# pqm_v2_page5.net
KiCad netlist of a schematic drawn in Altium Designer
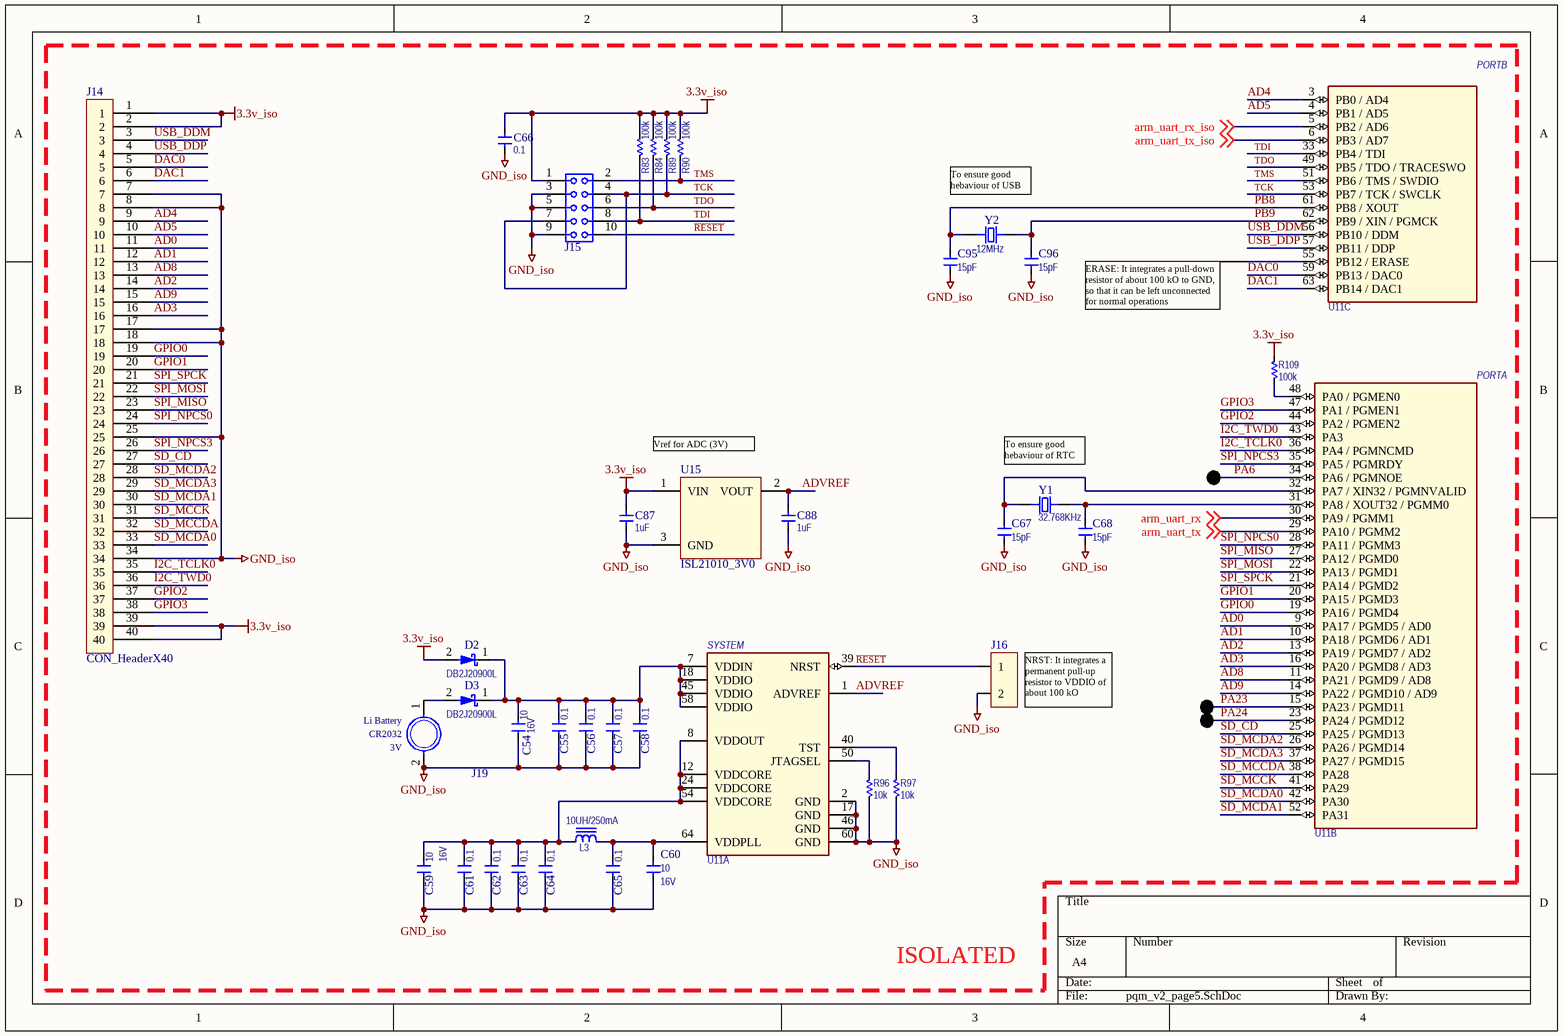
[diagram p0: pqm_v2_page5.SchDoc]

(export (version "E")
  (design (tool "Eeschema 10.0.6"))
  (components
    (comp (ref "C54")
      (value "10")
      (footprint "CAPC2013X110N")
      (description "CAP CER 10UF 16V 10% X6S 0805")
      (fields
        (field (name "MANUFACTURER") "TDK Corporation")
        (field (name "TOLERANCE") "10%")
        (field (name "VOLTAGE RATING") "16V")
      )
      (libsource (lib "pqm_v2_lib_cap") (part "CAP_C2012X6S1C106K085AC_TDK"))
    )
    (comp (ref "C55")
      (value "0.1")
      (footprint "CAPC2013X110N")
      (description "CAP CER 0.1UF 25V 10% X7R 0805")
      (fields (field (name "MANUFACTURER") "Yageo") (field (name "TOLERANCE") "10%"))
      (libsource (lib "pqm_v2_lib_cap") (part "CAP_CC0805KRX7R8BB104_YAGEO"))
    )
    (comp (ref "C56")
      (value "0.1")
      (footprint "CAPC2013X110N")
      (description "CAP CER 0.1UF 25V 10% X7R 0805")
      (fields (field (name "MANUFACTURER") "Yageo") (field (name "TOLERANCE") "10%"))
      (libsource (lib "pqm_v2_lib_cap") (part "CAP_CC0805KRX7R8BB104_YAGEO"))
    )
    (comp (ref "C57")
      (value "0.1")
      (footprint "CAPC2013X110N")
      (description "CAP CER 0.1UF 25V 10% X7R 0805")
      (fields (field (name "MANUFACTURER") "Yageo") (field (name "TOLERANCE") "10%"))
      (libsource (lib "pqm_v2_lib_cap") (part "CAP_CC0805KRX7R8BB104_YAGEO"))
    )
    (comp (ref "C58")
      (value "0.1")
      (footprint "CAPC2013X110N")
      (description "CAP CER 0.1UF 25V 10% X7R 0805")
      (fields (field (name "MANUFACTURER") "Yageo") (field (name "TOLERANCE") "10%"))
      (libsource (lib "pqm_v2_lib_cap") (part "CAP_CC0805KRX7R8BB104_YAGEO"))
    )
    (comp (ref "C59")
      (value "10")
      (footprint "CAPC2013X110N")
      (description "CAP CER 10UF 16V 10% X6S 0805")
      (fields
        (field (name "MANUFACTURER") "TDK Corporation")
        (field (name "TOLERANCE") "10%")
        (field (name "VOLTAGE RATING") "16V")
      )
      (libsource (lib "pqm_v2_lib_cap") (part "CAP_C2012X6S1C106K085AC_TDK"))
    )
    (comp (ref "C60")
      (value "10")
      (footprint "CAPC2013X110N")
      (description "CAP CER 10UF 16V 10% X6S 0805")
      (fields
        (field (name "MANUFACTURER") "TDK Corporation")
        (field (name "TOLERANCE") "10%")
        (field (name "VOLTAGE RATING") "16V")
      )
      (libsource (lib "pqm_v2_lib_cap") (part "CAP_C2012X6S1C106K085AC_TDK"))
    )
    (comp (ref "C61")
      (value "0.1")
      (footprint "CAPC2013X110N")
      (description "CAP CER 0.1UF 25V 10% X7R 0805")
      (fields (field (name "MANUFACTURER") "Yageo") (field (name "TOLERANCE") "10%"))
      (libsource (lib "pqm_v2_lib_cap") (part "CAP_CC0805KRX7R8BB104_YAGEO"))
    )
    (comp (ref "C62")
      (value "0.1")
      (footprint "CAPC2013X110N")
      (description "CAP CER 0.1UF 25V 10% X7R 0805")
      (fields (field (name "MANUFACTURER") "Yageo") (field (name "TOLERANCE") "10%"))
      (libsource (lib "pqm_v2_lib_cap") (part "CAP_CC0805KRX7R8BB104_YAGEO"))
    )
    (comp (ref "C63")
      (value "0.1")
      (footprint "CAPC2013X110N")
      (description "CAP CER 0.1UF 25V 10% X7R 0805")
      (fields (field (name "MANUFACTURER") "Yageo") (field (name "TOLERANCE") "10%"))
      (libsource (lib "pqm_v2_lib_cap") (part "CAP_CC0805KRX7R8BB104_YAGEO"))
    )
    (comp (ref "C64")
      (value "0.1")
      (footprint "CAPC2013X110N")
      (description "CAP CER 0.1UF 25V 10% X7R 0805")
      (fields (field (name "MANUFACTURER") "Yageo") (field (name "TOLERANCE") "10%"))
      (libsource (lib "pqm_v2_lib_cap") (part "CAP_CC0805KRX7R8BB104_YAGEO"))
    )
    (comp (ref "C65")
      (value "0.1")
      (footprint "CAPC2013X110N")
      (description "CAP CER 0.1UF 25V 10% X7R 0805")
      (fields (field (name "MANUFACTURER") "Yageo") (field (name "TOLERANCE") "10%"))
      (libsource (lib "pqm_v2_lib_cap") (part "CAP_CC0805KRX7R8BB104_YAGEO"))
    )
    (comp (ref "C66")
      (value "0.1")
      (footprint "CAPC2013X110N")
      (description "CAP CER 0.1UF 25V 10% X7R 0805")
      (fields (field (name "MANUFACTURER") "Yageo") (field (name "TOLERANCE") "10%"))
      (libsource (lib "pqm_v2_lib_cap") (part "CAP_CC0805KRX7R8BB104_YAGEO"))
    )
    (comp (ref "C67")
      (value "15pF")
      (footprint "CAPC2013X110N")
      (description "CAP CER 15PF 50V NP0 0805")
      (fields (field (name "MANUFACTURER") "Kemet") (field (name "DIGIKEY PART NUMBER") "399-7428-1-ND"))
      (libsource (lib "pqm_v2_lib_cap") (part "CAP_C0805X150J5GACTU_KEMET"))
    )
    (comp (ref "C68")
      (value "15pF")
      (footprint "CAPC2013X110N")
      (description "CAP CER 15PF 50V NP0 0805")
      (fields (field (name "MANUFACTURER") "Kemet") (field (name "DIGIKEY PART NUMBER") "399-7428-1-ND"))
      (libsource (lib "pqm_v2_lib_cap") (part "CAP_C0805X150J5GACTU_KEMET"))
    )
    (comp (ref "C87")
      (value "1uF")
      (footprint "CAPC2013X110N")
      (description "CAP CER 1UF 16V X7R 0805")
      (fields (field (name "MANUFACTURER") "YAGEO") (field (name "TOLERANCE") "10%"))
      (libsource (lib "pqm_v2_lib_cap") (part "CAP_CC0805KKX7R7BB105_YAGEO"))
    )
    (comp (ref "C88")
      (value "1uF")
      (footprint "CAPC2013X110N")
      (description "CAP CER 1UF 16V X7R 0805")
      (fields (field (name "MANUFACTURER") "YAGEO") (field (name "TOLERANCE") "10%"))
      (libsource (lib "pqm_v2_lib_cap") (part "CAP_CC0805KKX7R7BB105_YAGEO"))
    )
    (comp (ref "C95")
      (value "15pF")
      (footprint "CAPC2013X110N")
      (description "CAP CER 15PF 50V NP0 0805")
      (fields (field (name "MANUFACTURER") "Kemet") (field (name "DIGIKEY PART NUMBER") "399-7428-1-ND"))
      (libsource (lib "pqm_v2_lib_cap") (part "CAP_C0805X150J5GACTU_KEMET"))
    )
    (comp (ref "C96")
      (value "15pF")
      (footprint "CAPC2013X110N")
      (description "CAP CER 15PF 50V NP0 0805")
      (fields (field (name "MANUFACTURER") "Kemet") (field (name "DIGIKEY PART NUMBER") "399-7428-1-ND"))
      (libsource (lib "pqm_v2_lib_cap") (part "CAP_C0805X150J5GACTU_KEMET"))
    )
    (comp (ref "D2")
      (value "DB2J20900L")
      (footprint "SOD2512X097N")
      (description "DIODE SCHOTTKY 20V 500MA SMINI2")
      (fields
        (field (name "MANUFACTURER") "Panasonic")
        (field (name "DIGIKEY PART NUMBER") "DB2J20900LCT-ND")
      )
      (libsource (lib "pqm_v2_lib_diodos") (part "DIO_DB2J20900L_PANASONIC"))
    )
    (comp (ref "D3")
      (value "DB2J20900L")
      (footprint "SOD2512X097N")
      (description "DIODE SCHOTTKY 20V 500MA SMINI2")
      (fields
        (field (name "MANUFACTURER") "Panasonic")
        (field (name "DIGIKEY PART NUMBER") "DB2J20900LCT-ND")
      )
      (libsource (lib "pqm_v2_lib_diodos") (part "DIO_DB2J20900L_PANASONIC"))
    )
    (comp (ref "J14")
      (value "CON_HeaderX40")
      (footprint "HeaderX70")
      (libsource (lib "pqm_v2_lib_connectors") (part "CON_HeaderX40"))
    )
    (comp (ref "J15")
      (value "CON_20021121-00010C4LF_FCI")
      (footprint "FCI_20021121-00010C4LF")
      (description "CONN HEADER 10POS DL UNSHRD SMD")
      (fields (field (name "MANUFACTURER") "FCI") (field (name "DIGIKEY PART NUMBER") "609-3695-1-ND"))
      (libsource (lib "pqm_v2_lib_connectors") (part "CON_20021121-00010C4LF_FCI"))
    )
    (comp (ref "J16")
      (value "CON_RADX2")
      (footprint "RAD2")
      (libsource (lib "pqm_v2_lib_connectors") (part "CON_RADX2"))
    )
    (comp (ref "J19")
      (value "CON_BAT")
      (footprint "CON_BAT_2032")
      (description "HOLDER COINCELL 2032 RETAINRCLIP")
      (fields
        (field (name "DIGIKEY PART NUMBER") "BS-7-ND")
        (field (name "MOUSER PART NUMBER") "122-2420-GR")
      )
      (libsource (lib "pqm_v2_lib_connectors") (part "CON_BAT"))
    )
    (comp (ref "L3")
      (value "10UH/250mA")
      (footprint "INDC4532X170N")
      (description "FIXED IND 10UH 2A 65 MOHM SMD")
      (fields
        (field (name "MANUFACTURER") "Bourns Inc")
        (field (name "DIGIKEY PART NUMBER") "CM453232-100KLCT-ND")
      )
      (libsource (lib "pqm_v2_lib_mag") (part "MAG_CM453232-100KLCT_BOURNS"))
    )
    (comp (ref "R83")
      (value "100k")
      (footprint "RESC2013X065BN")
      (description "RES SMD 100K OHM 5% 1/8W 0805")
      (fields (field (name "TOLERANCE") "5%") (field (name "MANUFACTURER") "Yageo"))
      (libsource (lib "pqm_v2_lib_res") (part "RES_AC0805JR-07100KL_YAGEO"))
    )
    (comp (ref "R84")
      (value "100k")
      (footprint "RESC2013X065BN")
      (description "RES SMD 100K OHM 5% 1/8W 0805")
      (fields (field (name "TOLERANCE") "5%") (field (name "MANUFACTURER") "Yageo"))
      (libsource (lib "pqm_v2_lib_res") (part "RES_AC0805JR-07100KL_YAGEO"))
    )
    (comp (ref "R89")
      (value "100k")
      (footprint "RESC2013X065BN")
      (description "RES SMD 100K OHM 5% 1/8W 0805")
      (fields (field (name "TOLERANCE") "5%") (field (name "MANUFACTURER") "Yageo"))
      (libsource (lib "pqm_v2_lib_res") (part "RES_AC0805JR-07100KL_YAGEO"))
    )
    (comp (ref "R90")
      (value "100k")
      (footprint "RESC2013X065BN")
      (description "RES SMD 100K OHM 5% 1/8W 0805")
      (fields (field (name "TOLERANCE") "5%") (field (name "MANUFACTURER") "Yageo"))
      (libsource (lib "pqm_v2_lib_res") (part "RES_AC0805JR-07100KL_YAGEO"))
    )
    (comp (ref "R96")
      (value "10k")
      (footprint "RESC2013X065BN")
      (description "RES SMD 10K OHM 5% 1/8W 0805")
      (fields (field (name "TOLERANCE") "5%") (field (name "MANUFACTURER") "Yageo"))
      (libsource (lib "pqm_v2_lib_res") (part "RES_RC0805JR-0710KL_YAGEO"))
    )
    (comp (ref "R97")
      (value "10k")
      (footprint "RESC2013X065BN")
      (description "RES SMD 10K OHM 5% 1/8W 0805")
      (fields (field (name "TOLERANCE") "5%") (field (name "MANUFACTURER") "Yageo"))
      (libsource (lib "pqm_v2_lib_res") (part "RES_RC0805JR-0710KL_YAGEO"))
    )
    (comp (ref "R109")
      (value "100k")
      (footprint "RESC2013X065BN")
      (description "RES SMD 100K OHM 5% 1/8W 0805")
      (fields (field (name "TOLERANCE") "5%") (field (name "MANUFACTURER") "Yageo"))
      (libsource (lib "pqm_v2_lib_res") (part "RES_AC0805JR-07100KL_YAGEO"))
    )
    (comp (ref "U11")
      (value "IC_ATSAM4S8BA-AU_ATMEL")
      (footprint "TQFP50P1000X1000X160-64N")
      (description "IC MCU 32BIT 512KB FLASH 64LQFP")
      (fields (field (name "MANUFACTURER") "Atmel") (field (name "DIGIKEY PART NUMBER") "ATSAM4S8BA-AU-ND"))
      (libsource (lib "") (part "IC_ATSAM4S8BA-AU_ATMEL_1"))
    )
    (comp (ref "U15")
      (value "ISL21010_3V0")
      (footprint "SOT23-3M")
      (description "IC VREF SERIES 3V SOT23-3")
      (fields
        (field (name "DIGIKEY PART NUMBER") "ISL21010CFH330Z-TKCT-ND")
        (field (name "MANUFACTURER PART NUMBER") "ISL21010CFH330Z-TK")
      )
      (libsource (lib "pqm_v2_lib_ic") (part "IC_ISL21010_3V0_INTERSIL"))
    )
    (comp (ref "Y1")
      (value "32.768KHz")
      (footprint "XTAL3215X090N")
      (description "CRYSTAL 32.7680KHZ 12.5PF SMD")
      (fields (field (name "MANUFACTURER") "ECS") (field (name "DIGIKEY PART NUMBER") "XC1967CT-ND"))
      (libsource (lib "pqm_v2_lib_connectors") (part "MSC_ECS-.327-12.5-34S-TR_ECS"))
    )
    (comp (ref "Y2")
      (value "12MHz")
      (footprint "CSM-3X")
      (description "12 MHz ±30 ppm Cristales 20 pF 60 Ohm -10°C ~ 70°C Montaje en superficie HC49/US")
      (fields (field (name "MANUFACTURER") "ECS Inc.") (field (name "DIGIKEY PART NUMBER") "XC1770DKR-ND"))
      (libsource (lib "pqm_v2_lib_connectors") (part "MSC_ECS-120-20-3X-TR_ECS"))
    )
  )
  (nets
    (net (code "1") (name "/AD0") (class "Default")
      (node (ref "J14") (pin "11") (pinfunction "11_11") (pintype "passive"))
      (node (ref "U11") (pin "9") (pinfunction "PA17_/_PGMD5_/_AD0_9") (pintype "bidirectional"))
    )
    (net (code "2") (name "/AD1") (class "Default")
      (node (ref "J14") (pin "12") (pinfunction "12_12") (pintype "passive"))
      (node (ref "U11") (pin "10") (pinfunction "PA18_/_PGMD6_/_AD1_10") (pintype "bidirectional"))
    )
    (net (code "3") (name "/AD2") (class "Default")
      (node (ref "J14") (pin "14") (pinfunction "14_14") (pintype "passive"))
      (node (ref "U11") (pin "13") (pinfunction "PA19_/_PGMD7_/_AD2_13") (pintype "bidirectional"))
    )
    (net (code "4") (name "/AD3") (class "Default")
      (node (ref "J14") (pin "16") (pinfunction "16_16") (pintype "passive"))
      (node (ref "U11") (pin "16") (pinfunction "PA20_/_PGMD8_/_AD3_16") (pintype "bidirectional"))
    )
    (net (code "5") (name "/AD4") (class "Default")
      (node (ref "J14") (pin "9") (pinfunction "9_9") (pintype "passive"))
      (node (ref "U11") (pin "3") (pinfunction "PB0_/_AD4_3") (pintype "bidirectional"))
    )
    (net (code "6") (name "/AD5") (class "Default")
      (node (ref "J14") (pin "10") (pinfunction "10_10") (pintype "passive"))
      (node (ref "U11") (pin "4") (pinfunction "PB1_/_AD5_4") (pintype "bidirectional"))
    )
    (net (code "7") (name "/AD8") (class "Default")
      (node (ref "J14") (pin "13") (pinfunction "13_13") (pintype "passive"))
      (node (ref "U11") (pin "11") (pinfunction "PA21_/_PGMD9_/_AD8_11") (pintype "bidirectional"))
    )
    (net (code "8") (name "/AD9") (class "Default")
      (node (ref "J14") (pin "15") (pinfunction "15_15") (pintype "passive"))
      (node (ref "U11") (pin "14") (pinfunction "PA22_/_PGMD10_/_AD9_14") (pintype "bidirectional"))
    )
    (net (code "9") (name "/ADVREF") (class "Default")
      (node (ref "C88") (pin "1") (pinfunction "T1_1") (pintype "passive"))
      (node (ref "U11") (pin "1") (pinfunction "ADVREF_1") (pintype "power_in"))
      (node (ref "U15") (pin "2") (pinfunction "VOUT_2") (pintype "passive"))
    )
    (net (code "10") (name "/DAC0") (class "Default")
      (node (ref "J14") (pin "5") (pinfunction "5_5") (pintype "passive"))
      (node (ref "U11") (pin "59") (pinfunction "PB13_/_DAC0_59") (pintype "bidirectional"))
    )
    (net (code "11") (name "/DAC1") (class "Default")
      (node (ref "J14") (pin "6") (pinfunction "6_6") (pintype "passive"))
      (node (ref "U11") (pin "63") (pinfunction "PB14_/_DAC1_63") (pintype "bidirectional"))
    )
    (net (code "12") (name "/GPIO0") (class "Default")
      (node (ref "J14") (pin "19") (pinfunction "19_19") (pintype "passive"))
      (node (ref "U11") (pin "19") (pinfunction "PA16_/_PGMD4_19") (pintype "bidirectional"))
    )
    (net (code "13") (name "/GPIO1") (class "Default")
      (node (ref "J14") (pin "20") (pinfunction "20_20") (pintype "passive"))
      (node (ref "U11") (pin "20") (pinfunction "PA15_/_PGMD3_20") (pintype "bidirectional"))
    )
    (net (code "14") (name "/GPIO2") (class "Default")
      (node (ref "J14") (pin "37") (pinfunction "37_37") (pintype "passive"))
      (node (ref "U11") (pin "44") (pinfunction "PA2_/_PGMEN2_44") (pintype "bidirectional"))
    )
    (net (code "15") (name "/GPIO3") (class "Default")
      (node (ref "J14") (pin "38") (pinfunction "38_38") (pintype "passive"))
      (node (ref "U11") (pin "47") (pinfunction "PA1_/_PGMEN1_47") (pintype "bidirectional"))
    )
    (net (code "16") (name "/I2C_TCLK0") (class "Default")
      (node (ref "J14") (pin "35") (pinfunction "35_35") (pintype "passive"))
      (node (ref "U11") (pin "36") (pinfunction "PA4_/_PGMNCMD_36") (pintype "bidirectional"))
    )
    (net (code "17") (name "/I2C_TWD0") (class "Default")
      (node (ref "J14") (pin "36") (pinfunction "36_36") (pintype "passive"))
      (node (ref "U11") (pin "43") (pinfunction "PA3_43") (pintype "bidirectional"))
    )
    (net (code "18") (name "/PA6") (class "Default")
      (node (ref "U11") (pin "34") (pinfunction "PA6_/_PGMNOE_34") (pintype "bidirectional"))
    )
    (net (code "19") (name "/PA23") (class "Default")
      (node (ref "U11") (pin "15") (pinfunction "PA23_/_PGMD11_15") (pintype "bidirectional"))
    )
    (net (code "20") (name "/PA24") (class "Default")
      (node (ref "U11") (pin "23") (pinfunction "PA24_/_PGMD12_23") (pintype "bidirectional"))
    )
    (net (code "21") (name "/PB8") (class "Default")
      (node (ref "C95") (pin "1") (pinfunction "T1_1") (pintype "passive"))
      (node (ref "U11") (pin "61") (pinfunction "PB8_/_XOUT_61") (pintype "bidirectional"))
      (node (ref "Y2") (pin "1") (pinfunction "1_1") (pintype "passive"))
    )
    (net (code "22") (name "/PB9") (class "Default")
      (node (ref "C96") (pin "1") (pinfunction "T1_1") (pintype "passive"))
      (node (ref "U11") (pin "62") (pinfunction "PB9_/_XIN_/_PGMCK_62") (pintype "bidirectional"))
      (node (ref "Y2") (pin "2") (pinfunction "2_2") (pintype "passive"))
    )
    (net (code "23") (name "/SD_CD") (class "Default")
      (node (ref "J14") (pin "27") (pinfunction "27_27") (pintype "passive"))
      (node (ref "U11") (pin "25") (pinfunction "PA25_/_PGMD13_25") (pintype "bidirectional"))
    )
    (net (code "24") (name "/SD_MCCDA") (class "Default")
      (node (ref "J14") (pin "32") (pinfunction "32_32") (pintype "passive"))
      (node (ref "U11") (pin "38") (pinfunction "PA28_38") (pintype "bidirectional"))
    )
    (net (code "25") (name "/SD_MCCK") (class "Default")
      (node (ref "J14") (pin "31") (pinfunction "31_31") (pintype "passive"))
      (node (ref "U11") (pin "41") (pinfunction "PA29_41") (pintype "bidirectional"))
    )
    (net (code "26") (name "/SD_MCDA0") (class "Default")
      (node (ref "J14") (pin "33") (pinfunction "33_33") (pintype "passive"))
      (node (ref "U11") (pin "42") (pinfunction "PA30_42") (pintype "bidirectional"))
    )
    (net (code "27") (name "/SD_MCDA1") (class "Default")
      (node (ref "J14") (pin "30") (pinfunction "30_30") (pintype "passive"))
      (node (ref "U11") (pin "52") (pinfunction "PA31_52") (pintype "bidirectional"))
    )
    (net (code "28") (name "/SD_MCDA2") (class "Default")
      (node (ref "J14") (pin "28") (pinfunction "28_28") (pintype "passive"))
      (node (ref "U11") (pin "26") (pinfunction "PA26_/_PGMD14_26") (pintype "bidirectional"))
    )
    (net (code "29") (name "/SD_MCDA3") (class "Default")
      (node (ref "J14") (pin "29") (pinfunction "29_29") (pintype "passive"))
      (node (ref "U11") (pin "37") (pinfunction "PA27_/_PGMD15_37") (pintype "bidirectional"))
    )
    (net (code "30") (name "/SPI_MISO") (class "Default")
      (node (ref "J14") (pin "23") (pinfunction "23_23") (pintype "passive"))
      (node (ref "U11") (pin "27") (pinfunction "PA12_/_PGMD0_27") (pintype "bidirectional"))
    )
    (net (code "31") (name "/SPI_MOSI") (class "Default")
      (node (ref "J14") (pin "22") (pinfunction "22_22") (pintype "passive"))
      (node (ref "U11") (pin "22") (pinfunction "PA13_/_PGMD1_22") (pintype "bidirectional"))
    )
    (net (code "32") (name "/SPI_NPCS0") (class "Default")
      (node (ref "J14") (pin "24") (pinfunction "24_24") (pintype "passive"))
      (node (ref "U11") (pin "28") (pinfunction "PA11_/_PGMM3_28") (pintype "bidirectional"))
    )
    (net (code "33") (name "/SPI_NPCS3") (class "Default")
      (node (ref "J14") (pin "26") (pinfunction "26_26") (pintype "passive"))
      (node (ref "U11") (pin "35") (pinfunction "PA5_/_PGMRDY_35") (pintype "bidirectional"))
    )
    (net (code "34") (name "/SPI_SPCK") (class "Default")
      (node (ref "J14") (pin "21") (pinfunction "21_21") (pintype "passive"))
      (node (ref "U11") (pin "21") (pinfunction "PA14_/_PGMD2_21") (pintype "bidirectional"))
    )
    (net (code "35") (name "/TCK") (class "Default")
      (node (ref "J15") (pin "4") (pinfunction "4_4") (pintype "passive"))
      (node (ref "J15") (pin "7") (pinfunction "7_7") (pintype "passive"))
      (node (ref "R89") (pin "1") (pinfunction "T1_1") (pintype "passive"))
      (node (ref "U11") (pin "53") (pinfunction "PB7_/_TCK_/_SWCLK_53") (pintype "bidirectional"))
    )
    (net (code "36") (name "/TDI") (class "Default")
      (node (ref "J15") (pin "8") (pinfunction "8_8") (pintype "passive"))
      (node (ref "R83") (pin "1") (pinfunction "T1_1") (pintype "passive"))
      (node (ref "U11") (pin "33") (pinfunction "PB4_/_TDI_33") (pintype "bidirectional"))
    )
    (net (code "37") (name "/TDO") (class "Default")
      (node (ref "J15") (pin "6") (pinfunction "6_6") (pintype "passive"))
      (node (ref "R84") (pin "1") (pinfunction "T1_1") (pintype "passive"))
      (node (ref "U11") (pin "49") (pinfunction "PB5_/_TDO_/_TRACESWO_49") (pintype "bidirectional"))
    )
    (net (code "38") (name "/TMS") (class "Default")
      (node (ref "J15") (pin "2") (pinfunction "2_2") (pintype "passive"))
      (node (ref "R90") (pin "1") (pinfunction "T1_1") (pintype "passive"))
      (node (ref "U11") (pin "51") (pinfunction "PB6_/_TMS_/_SWDIO_51") (pintype "bidirectional"))
    )
    (net (code "39") (name "/USB_DDM") (class "Default")
      (node (ref "J14") (pin "3") (pinfunction "3_3") (pintype "passive"))
      (node (ref "U11") (pin "56") (pinfunction "PB10_/_DDM_56") (pintype "bidirectional"))
    )
    (net (code "40") (name "/USB_DDP") (class "Default")
      (node (ref "J14") (pin "4") (pinfunction "4_4") (pintype "passive"))
      (node (ref "U11") (pin "57") (pinfunction "PB11_/_DDP_57") (pintype "bidirectional"))
    )
    (net (code "41") (name "/~{RESET}") (class "Default")
      (node (ref "J15") (pin "10") (pinfunction "10_10") (pintype "passive"))
      (node (ref "J16") (pin "1") (pinfunction "1_1") (pintype "passive"))
      (node (ref "U11") (pin "39") (pinfunction "NRST_39") (pintype "bidirectional"))
    )
    (net (code "42") (name "3.3v_iso") (class "Default")
      (node (ref "C66") (pin "1") (pinfunction "T1_1") (pintype "passive"))
      (node (ref "C87") (pin "1") (pinfunction "T1_1") (pintype "passive"))
      (node (ref "D2") (pin "2") (pinfunction "A_2") (pintype "passive"))
      (node (ref "J14") (pin "1") (pinfunction "1_1") (pintype "passive"))
      (node (ref "J14") (pin "2") (pinfunction "2_2") (pintype "passive"))
      (node (ref "J14") (pin "39") (pinfunction "39_39") (pintype "passive"))
      (node (ref "J14") (pin "40") (pinfunction "40_40") (pintype "passive"))
      (node (ref "J15") (pin "1") (pinfunction "1_1") (pintype "passive"))
      (node (ref "R109") (pin "2") (pinfunction "T2_2") (pintype "passive"))
      (node (ref "R83") (pin "2") (pinfunction "T2_2") (pintype "passive"))
      (node (ref "R84") (pin "2") (pinfunction "T2_2") (pintype "passive"))
      (node (ref "R89") (pin "2") (pinfunction "T2_2") (pintype "passive"))
      (node (ref "R90") (pin "2") (pinfunction "T2_2") (pintype "passive"))
      (node (ref "U15") (pin "1") (pinfunction "VIN_1") (pintype "passive"))
    )
    (net (code "43") (name "GND_iso") (class "Default")
      (node (ref "C54") (pin "2") (pinfunction "T2_2") (pintype "passive"))
      (node (ref "C55") (pin "2") (pinfunction "T2_2") (pintype "passive"))
      (node (ref "C56") (pin "2") (pinfunction "T2_2") (pintype "passive"))
      (node (ref "C57") (pin "2") (pinfunction "T2_2") (pintype "passive"))
      (node (ref "C58") (pin "2") (pinfunction "T2_2") (pintype "passive"))
      (node (ref "C59") (pin "2") (pinfunction "T2_2") (pintype "passive"))
      (node (ref "C60") (pin "2") (pinfunction "T2_2") (pintype "passive"))
      (node (ref "C61") (pin "1") (pinfunction "T1_1") (pintype "passive"))
      (node (ref "C62") (pin "1") (pinfunction "T1_1") (pintype "passive"))
      (node (ref "C63") (pin "1") (pinfunction "T1_1") (pintype "passive"))
      (node (ref "C64") (pin "1") (pinfunction "T1_1") (pintype "passive"))
      (node (ref "C65") (pin "1") (pinfunction "T1_1") (pintype "passive"))
      (node (ref "C66") (pin "2") (pinfunction "T2_2") (pintype "passive"))
      (node (ref "C67") (pin "2") (pinfunction "T2_2") (pintype "passive"))
      (node (ref "C68") (pin "2") (pinfunction "T2_2") (pintype "passive"))
      (node (ref "C87") (pin "2") (pinfunction "T2_2") (pintype "passive"))
      (node (ref "C88") (pin "2") (pinfunction "T2_2") (pintype "passive"))
      (node (ref "C95") (pin "2") (pinfunction "T2_2") (pintype "passive"))
      (node (ref "C96") (pin "2") (pinfunction "T2_2") (pintype "passive"))
      (node (ref "J14") (pin "17") (pinfunction "17_17") (pintype "passive"))
      (node (ref "J14") (pin "18") (pinfunction "18_18") (pintype "passive"))
      (node (ref "J14") (pin "25") (pinfunction "25_25") (pintype "passive"))
      (node (ref "J14") (pin "34") (pinfunction "34_34") (pintype "passive"))
      (node (ref "J14") (pin "7") (pinfunction "7_7") (pintype "passive"))
      (node (ref "J14") (pin "8") (pinfunction "8_8") (pintype "passive"))
      (node (ref "J15") (pin "3") (pinfunction "3_3") (pintype "passive"))
      (node (ref "J15") (pin "5") (pinfunction "5_5") (pintype "passive"))
      (node (ref "J15") (pin "9") (pinfunction "9_9") (pintype "passive"))
      (node (ref "J16") (pin "2") (pinfunction "2_2") (pintype "passive"))
      (node (ref "J19") (pin "2") (pinfunction "2_2") (pintype "passive"))
      (node (ref "R96") (pin "1") (pinfunction "T1_1") (pintype "passive"))
      (node (ref "R97") (pin "1") (pinfunction "T1_1") (pintype "passive"))
      (node (ref "U11") (pin "17") (pinfunction "GND_17") (pintype "power_in"))
      (node (ref "U11") (pin "2") (pinfunction "GND_2") (pintype "power_in"))
      (node (ref "U11") (pin "46") (pinfunction "GND_46") (pintype "power_in"))
      (node (ref "U11") (pin "60") (pinfunction "GND_60") (pintype "power_in"))
      (node (ref "U15") (pin "3") (pinfunction "GND_3") (pintype "passive"))
    )
    (net (code "44") (name "Net-(C54-T1)") (class "Default")
      (node (ref "C54") (pin "1") (pinfunction "T1_1") (pintype "passive"))
      (node (ref "C55") (pin "1") (pinfunction "T1_1") (pintype "passive"))
      (node (ref "C56") (pin "1") (pinfunction "T1_1") (pintype "passive"))
      (node (ref "C57") (pin "1") (pinfunction "T1_1") (pintype "passive"))
      (node (ref "C58") (pin "1") (pinfunction "T1_1") (pintype "passive"))
      (node (ref "D2") (pin "1") (pinfunction "K_1") (pintype "passive"))
      (node (ref "D3") (pin "1") (pinfunction "K_1") (pintype "passive"))
      (node (ref "U11") (pin "18") (pinfunction "VDDIO_18") (pintype "power_in"))
      (node (ref "U11") (pin "45") (pinfunction "VDDIO_45") (pintype "power_in"))
      (node (ref "U11") (pin "58") (pinfunction "VDDIO_58") (pintype "power_in"))
      (node (ref "U11") (pin "7") (pinfunction "VDDIN_7") (pintype "power_in"))
    )
    (net (code "45") (name "Net-(C59-T1)") (class "Default")
      (node (ref "C59") (pin "1") (pinfunction "T1_1") (pintype "passive"))
      (node (ref "C61") (pin "2") (pinfunction "T2_2") (pintype "passive"))
      (node (ref "C62") (pin "2") (pinfunction "T2_2") (pintype "passive"))
      (node (ref "C63") (pin "2") (pinfunction "T2_2") (pintype "passive"))
      (node (ref "C64") (pin "2") (pinfunction "T2_2") (pintype "passive"))
      (node (ref "L3") (pin "1") (pinfunction "1_1") (pintype "passive"))
      (node (ref "U11") (pin "12") (pinfunction "VDDCORE_12") (pintype "power_in"))
      (node (ref "U11") (pin "24") (pinfunction "VDDCORE_24") (pintype "power_in"))
      (node (ref "U11") (pin "54") (pinfunction "VDDCORE_54") (pintype "power_in"))
      (node (ref "U11") (pin "8") (pinfunction "VDDOUT_8") (pintype "power_in"))
    )
    (net (code "46") (name "Net-(C60-T1)") (class "Default")
      (node (ref "C60") (pin "1") (pinfunction "T1_1") (pintype "passive"))
      (node (ref "C65") (pin "2") (pinfunction "T2_2") (pintype "passive"))
      (node (ref "L3") (pin "2") (pinfunction "2_2") (pintype "passive"))
      (node (ref "U11") (pin "64") (pinfunction "VDDPLL_64") (pintype "power_in"))
    )
    (net (code "47") (name "Net-(C67-T1)") (class "Default")
      (node (ref "C67") (pin "1") (pinfunction "T1_1") (pintype "passive"))
      (node (ref "U11") (pin "32") (pinfunction "PA7_/_XIN32_/_PGMNVALID_32") (pintype "bidirectional"))
      (node (ref "Y1") (pin "1") (pinfunction "1_1") (pintype "passive"))
    )
    (net (code "48") (name "Net-(C68-T1)") (class "Default")
      (node (ref "C68") (pin "1") (pinfunction "T1_1") (pintype "passive"))
      (node (ref "U11") (pin "31") (pinfunction "PA8_/_XOUT32_/_PGMM0_31") (pintype "bidirectional"))
      (node (ref "Y1") (pin "2") (pinfunction "2_2") (pintype "passive"))
    )
    (net (code "49") (name "Net-(D3-A)") (class "Default")
      (node (ref "D3") (pin "2") (pinfunction "A_2") (pintype "passive"))
      (node (ref "J19") (pin "1") (pinfunction "1_1") (pintype "passive"))
    )
    (net (code "50") (name "Net-(R96-T2)") (class "Default")
      (node (ref "R96") (pin "2") (pinfunction "T2_2") (pintype "passive"))
      (node (ref "U11") (pin "50") (pinfunction "JTAGSEL_50") (pintype "passive"))
    )
    (net (code "51") (name "Net-(R97-T2)") (class "Default")
      (node (ref "R97") (pin "2") (pinfunction "T2_2") (pintype "passive"))
      (node (ref "U11") (pin "40") (pinfunction "TST_40") (pintype "passive"))
    )
    (net (code "52") (name "Net-(R109-T1)") (class "Default")
      (node (ref "R109") (pin "1") (pinfunction "T1_1") (pintype "passive"))
      (node (ref "U11") (pin "48") (pinfunction "PA0_/_PGMEN0_48") (pintype "bidirectional"))
    )
    (net (code "53") (name "arm_uart_rx") (class "Default")
      (node (ref "U11") (pin "30") (pinfunction "PA9_/_PGMM1_30") (pintype "bidirectional"))
    )
    (net (code "54") (name "arm_uart_rx_iso") (class "Default")
      (node (ref "U11") (pin "5") (pinfunction "PB2_/_AD6_5") (pintype "bidirectional"))
    )
    (net (code "55") (name "arm_uart_tx") (class "Default")
      (node (ref "U11") (pin "29") (pinfunction "PA10_/_PGMM2_29") (pintype "bidirectional"))
    )
    (net (code "56") (name "arm_uart_tx_iso") (class "Default")
      (node (ref "U11") (pin "6") (pinfunction "PB3_/_AD7_6") (pintype "bidirectional"))
    )
    (net (code "57") (name "unconnected-(U11C-PB12_{slash}_ERASE-Pad55)") (class "Default")
      (node (ref "U11") (pin "55") (pinfunction "PB12_/_ERASE_55") (pintype "bidirectional"))
    )
  )
)
